# PAGE1.net
KiCad netlist of a schematic drawn in Altium Designer
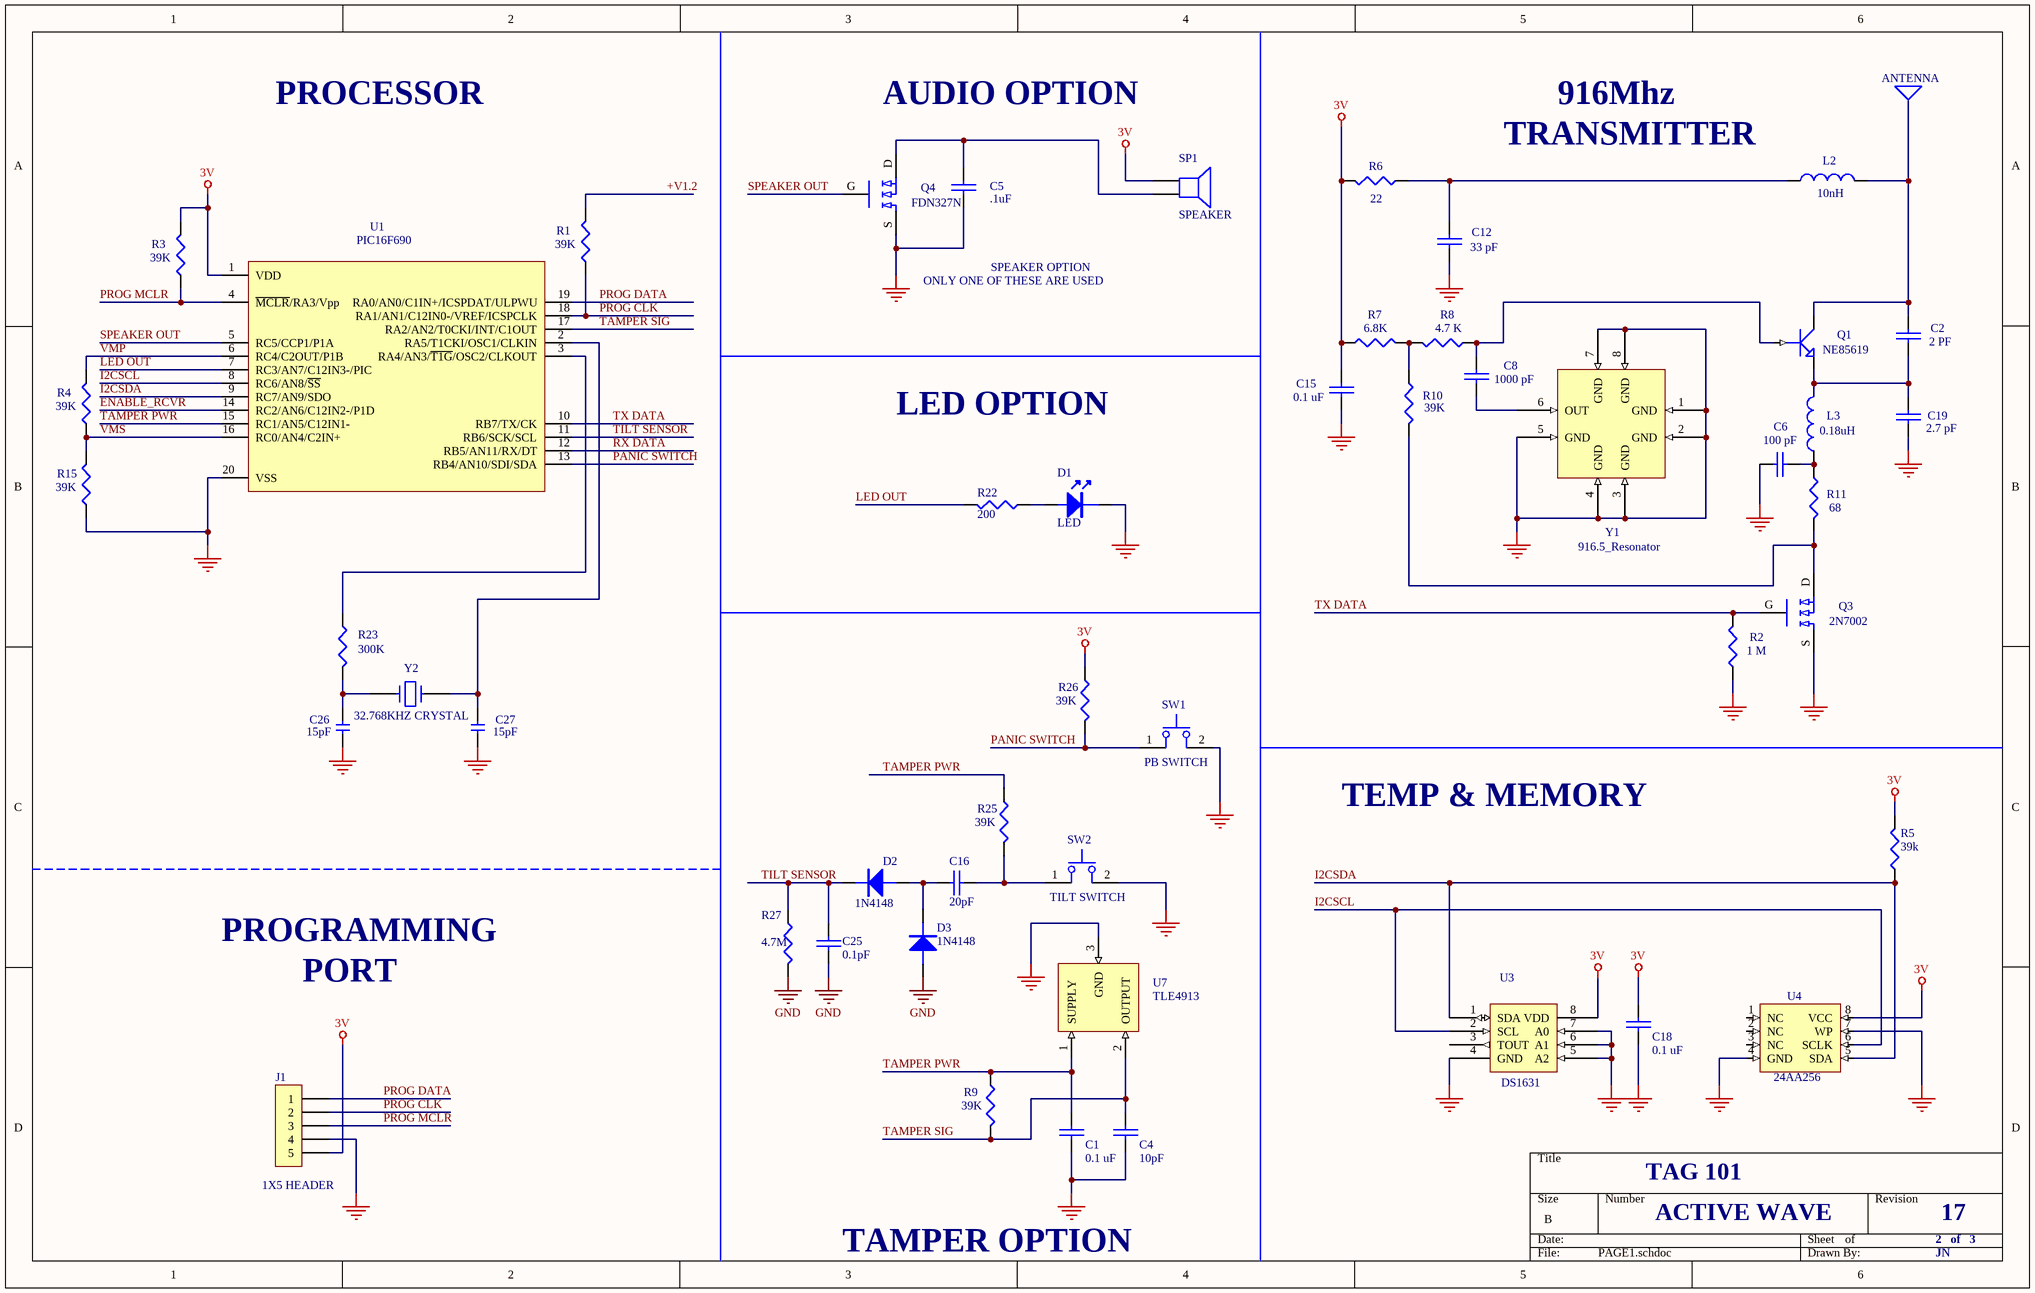
[diagram p0: PAGE1.schdoc]

(export (version "E")
  (design (tool "Eeschema 10.0.6"))
  (components
    (comp (ref "C1")
      (value "0.1 uF")
      (footprint "0603")
      (description "Capacitor")
      (libsource (lib "*") (part "CAP"))
    )
    (comp (ref "C2")
      (value "2 PF")
      (footprint "0603")
      (description "Capacitor")
      (libsource (lib "*") (part "CAP"))
    )
    (comp (ref "C4")
      (value "10pF")
      (footprint "0603")
      (description "Capacitor")
      (libsource (lib "*") (part "CAP"))
    )
    (comp (ref "C5")
      (value ".1uF")
      (footprint "0603")
      (description "Capacitor")
      (libsource (lib "*") (part "CAP"))
    )
    (comp (ref "C6")
      (value "100 pF")
      (footprint "0603")
      (description "Capacitor")
      (libsource (lib "*") (part "CAP"))
    )
    (comp (ref "C8")
      (value "1000 pF")
      (footprint "0603")
      (description "Capacitor")
      (libsource (lib "*") (part "CAP"))
    )
    (comp (ref "C12")
      (value "33 pF")
      (footprint "0603")
      (description "Capacitor")
      (libsource (lib "*") (part "CAP"))
    )
    (comp (ref "C15")
      (value "0.1 uF")
      (footprint "0603")
      (description "Capacitor")
      (libsource (lib "*") (part "CAP"))
    )
    (comp (ref "C16")
      (value "20pF")
      (footprint "0603")
      (description "Capacitor")
      (libsource (lib "*") (part "CAP"))
    )
    (comp (ref "C18")
      (value "0.1 uF")
      (footprint "0603")
      (description "Capacitor")
      (libsource (lib "*") (part "CAP"))
    )
    (comp (ref "C19")
      (value "2.7 pF")
      (footprint "0603")
      (description "Capacitor")
      (libsource (lib "*") (part "CAP"))
    )
    (comp (ref "C25")
      (value "0.1pF")
      (footprint "0603")
      (description "Capacitor")
      (libsource (lib "*") (part "CAP"))
    )
    (comp (ref "C26") (value "15pF") (footprint "0603") (libsource (lib "*") (part "C")))
    (comp (ref "C27") (value "15pF") (footprint "0603") (libsource (lib "*") (part "C")))
    (comp (ref "D1") (value "LED") (footprint "LED STANLEY H_1105W") (libsource (lib "*") (part "LED")))
    (comp (ref "D2")
      (value "1N4148")
      (footprint "sod123_021405")
      (description "Diode")
      (libsource (lib "*") (part "DIODE"))
    )
    (comp (ref "D3")
      (value "1N4148")
      (footprint "sod123_021405")
      (description "Diode")
      (libsource (lib "*") (part "DIODE"))
    )
    (comp (ref "J1")
      (value "1X5 HEADER")
      (footprint "1X5 HEADER")
      (description "Connector")
      (libsource (lib "*") (part "CON5"))
    )
    (comp (ref "L2") (value "10nH") (footprint "0603") (libsource (lib "*") (part "INDUCTOR")))
    (comp (ref "L3") (value "0.18uH") (footprint "0603") (libsource (lib "*") (part "INDUCTOR")))
    (comp (ref "Q1")
      (value "NE85619")
      (footprint "3 PIN ULTRA SUPER MINI MOLD")
      (description "NPN Transistor")
      (libsource (lib "*") (part "NPN1"))
    )
    (comp (ref "Q3") (value "2N7002") (libsource (lib "*") (part "FET 2")))
    (comp (ref "Q4") (value "FDN327N") (libsource (lib "*") (part "FET 2")))
    (comp (ref "R1") (value "39K") (footprint "0603") (libsource (lib "*") (part "RESISTOR")))
    (comp (ref "R2") (value "1 M") (footprint "0603") (libsource (lib "*") (part "RESISTOR")))
    (comp (ref "R3") (value "39K") (footprint "0603") (libsource (lib "*") (part "RESISTOR")))
    (comp (ref "R4") (value "39K") (footprint "0603") (libsource (lib "*") (part "RESISTOR")))
    (comp (ref "R5") (value "39k") (footprint "0603") (libsource (lib "*") (part "RESISTOR")))
    (comp (ref "R6") (value "22") (footprint "0603") (libsource (lib "*") (part "RESISTOR")))
    (comp (ref "R7") (value "6.8K") (footprint "0603") (libsource (lib "*") (part "RESISTOR")))
    (comp (ref "R8") (value "4.7 K") (footprint "0603") (libsource (lib "*") (part "RESISTOR")))
    (comp (ref "R9") (value "39K") (footprint "0603") (libsource (lib "*") (part "RESISTOR")))
    (comp (ref "R10") (value "39K") (footprint "0603") (libsource (lib "*") (part "RESISTOR")))
    (comp (ref "R11") (value "68") (footprint "0603") (libsource (lib "*") (part "RES1")))
    (comp (ref "R15") (value "39K") (footprint "0603") (libsource (lib "*") (part "RESISTOR")))
    (comp (ref "R22") (value "200") (footprint "0603") (libsource (lib "*") (part "RES1")))
    (comp (ref "R23") (value "300K") (footprint "0603") (libsource (lib "*") (part "RESISTOR")))
    (comp (ref "R25") (value "39K") (footprint "0603") (libsource (lib "*") (part "RESISTOR")))
    (comp (ref "R26") (value "39K") (footprint "0603") (libsource (lib "*") (part "RESISTOR")))
    (comp (ref "R27") (value "4.7M") (footprint "0603") (libsource (lib "*") (part "RESISTOR")))
    (comp (ref "SP1") (value "SPEAKER") (footprint "SMT_1028-S-R") (libsource (lib "*") (part "SPEAKER")))
    (comp (ref "SW1")
      (value "PB SWITCH")
      (footprint "SWITCH PB REVERSED_082907")
      (libsource (lib "Common") (part "SWITCH PB"))
    )
    (comp (ref "SW2")
      (value "TILT SWITCH")
      (footprint "SQ-SEN-200")
      (libsource (lib "Common") (part "SWITCH PB"))
    )
    (comp (ref "U1") (value "PIC16F690") (libsource (lib "*") (part "PIC16F690")))
    (comp (ref "U3") (value "DS1631") (footprint "SO8 SMALL") (libsource (lib "*") (part "DS1631")))
    (comp (ref "U4") (value "24AA256") (footprint "SO8") (libsource (lib "*") (part "24AA256")))
    (comp (ref "U7") (value "TLE4913") (footprint "SOT23W") (libsource (lib "*") (part "HALL EFFECT SWITCH")))
    (comp (ref "Y1")
      (value "916.5_Resonator")
      (footprint "RESONATOR")
      (libsource (lib "*") (part "RESONATOR"))
    )
    (comp (ref "Y2")
      (value "32.768KHZ CRYSTAL")
      (footprint "CRYSTAL ABRACON ABS07")
      (description "Crystal")
      (libsource (lib "*") (part "CRYSTAL"))
    )
  )
  (nets
    (net (code "1") (name "/+V1.2") (class "Default")
      (node (ref "R1") (pin "2") (pinfunction "2_2") (pintype "passive"))
    )
    (net (code "2") (name "/ENABLE_RCVR") (class "Default")
      (node (ref "U1") (pin "14") (pinfunction "RC2/AN6/C12IN2-/P1D_14") (pintype "passive"))
    )
    (net (code "3") (name "/I2CSCL") (class "Default")
      (node (ref "U1") (pin "8") (pinfunction "RC6/AN8/~{SS}_8") (pintype "passive"))
      (node (ref "U3") (pin "2") (pinfunction "SCL_2") (pintype "input"))
      (node (ref "U4") (pin "6") (pinfunction "SCLK_6") (pintype "input"))
    )
    (net (code "4") (name "/I2CSDA") (class "Default")
      (node (ref "R5") (pin "1") (pinfunction "1_1") (pintype "passive"))
      (node (ref "U1") (pin "9") (pinfunction "RC7/AN9/SDO_9") (pintype "passive"))
      (node (ref "U3") (pin "1") (pinfunction "SDA_1") (pintype "bidirectional"))
      (node (ref "U4") (pin "5") (pinfunction "SDA_5") (pintype "input"))
    )
    (net (code "5") (name "/LED OUT") (class "Default")
      (node (ref "R22") (pin "2") (pinfunction "2_2") (pintype "passive"))
      (node (ref "U1") (pin "7") (pinfunction "RC3/AN7/C12IN3-/PIC_7") (pintype "passive"))
    )
    (net (code "6") (name "/PANIC SWITCH") (class "Default")
      (node (ref "R26") (pin "2") (pinfunction "2_2") (pintype "passive"))
      (node (ref "SW1") (pin "1") (pinfunction "1_1") (pintype "passive"))
      (node (ref "U1") (pin "13") (pinfunction "RB4/AN10/SDI/SDA_13") (pintype "passive"))
    )
    (net (code "7") (name "/PROG CLK") (class "Default")
      (node (ref "J1") (pin "2") (pinfunction "2_2") (pintype "passive"))
      (node (ref "R1") (pin "1") (pinfunction "1_1") (pintype "passive"))
      (node (ref "U1") (pin "18") (pinfunction "RA1/AN1/C12IN0-/VREF/ICSPCLK_18") (pintype "passive"))
    )
    (net (code "8") (name "/PROG DATA") (class "Default")
      (node (ref "J1") (pin "1") (pinfunction "1_1") (pintype "passive"))
      (node (ref "U1") (pin "19") (pinfunction "RA0/AN0/C1IN+/ICSPDAT/ULPWU_19") (pintype "passive"))
    )
    (net (code "9") (name "/PROG MCLR") (class "Default")
      (node (ref "J1") (pin "3") (pinfunction "3_3") (pintype "passive"))
      (node (ref "R3") (pin "1") (pinfunction "1_1") (pintype "passive"))
      (node (ref "U1") (pin "4") (pinfunction "~{MCLR}/RA3/Vpp_4") (pintype "passive"))
    )
    (net (code "10") (name "/RX DATA") (class "Default")
      (node (ref "U1") (pin "12") (pinfunction "RB5/AN11/RX/DT_12") (pintype "passive"))
    )
    (net (code "11") (name "/SPEAKER OUT") (class "Default")
      (node (ref "Q4") (pin "G") (pinfunction "G_G") (pintype "passive"))
      (node (ref "U1") (pin "5") (pinfunction "RC5/CCP1/P1A_5") (pintype "passive"))
    )
    (net (code "12") (name "/TAMPER PWR") (class "Default")
      (node (ref "C1") (pin "1") (pinfunction "1_1") (pintype "passive"))
      (node (ref "R25") (pin "1") (pinfunction "1_1") (pintype "passive"))
      (node (ref "R9") (pin "1") (pinfunction "1_1") (pintype "passive"))
      (node (ref "U1") (pin "15") (pinfunction "RC1/AN5/C12IN1-_15") (pintype "passive"))
      (node (ref "U7") (pin "1") (pinfunction "SUPPLY_1") (pintype "input"))
    )
    (net (code "13") (name "/TAMPER SIG") (class "Default")
      (node (ref "C4") (pin "1") (pinfunction "1_1") (pintype "passive"))
      (node (ref "R9") (pin "2") (pinfunction "2_2") (pintype "passive"))
      (node (ref "U1") (pin "17") (pinfunction "RA2/AN2/T0CKI/INT/C1OUT_17") (pintype "passive"))
      (node (ref "U7") (pin "2") (pinfunction "OUTPUT_2") (pintype "input"))
    )
    (net (code "14") (name "/TILT SENSOR") (class "Default")
      (node (ref "C25") (pin "1") (pinfunction "1_1") (pintype "passive"))
      (node (ref "D2") (pin "K") (pinfunction "K_K") (pintype "passive"))
      (node (ref "R27") (pin "1") (pinfunction "1_1") (pintype "passive"))
      (node (ref "U1") (pin "11") (pinfunction "RB6/SCK/SCL_11") (pintype "passive"))
    )
    (net (code "15") (name "/TX DATA") (class "Default")
      (node (ref "Q3") (pin "G") (pinfunction "G_G") (pintype "passive"))
      (node (ref "R2") (pin "2") (pinfunction "2_2") (pintype "passive"))
      (node (ref "U1") (pin "10") (pinfunction "RB7/TX/CK_10") (pintype "passive"))
    )
    (net (code "16") (name "/VMP") (class "Default")
      (node (ref "R4") (pin "2") (pinfunction "2_2") (pintype "passive"))
      (node (ref "U1") (pin "6") (pinfunction "RC4/C2OUT/P1B_6") (pintype "passive"))
    )
    (net (code "17") (name "/VMS") (class "Default")
      (node (ref "R15") (pin "2") (pinfunction "2_2") (pintype "passive"))
      (node (ref "R4") (pin "1") (pinfunction "1_1") (pintype "passive"))
      (node (ref "U1") (pin "16") (pinfunction "RC0/AN4/C2IN+_16") (pintype "passive"))
    )
    (net (code "18") (name "3V") (class "Default")
      (node (ref "C15") (pin "1") (pinfunction "1_1") (pintype "passive"))
      (node (ref "C18") (pin "1") (pinfunction "1_1") (pintype "passive"))
      (node (ref "J1") (pin "5") (pinfunction "5_5") (pintype "passive"))
      (node (ref "R26") (pin "1") (pinfunction "1_1") (pintype "passive"))
      (node (ref "R3") (pin "2") (pinfunction "2_2") (pintype "passive"))
      (node (ref "R5") (pin "2") (pinfunction "2_2") (pintype "passive"))
      (node (ref "R6") (pin "2") (pinfunction "2_2") (pintype "passive"))
      (node (ref "R7") (pin "1") (pinfunction "1_1") (pintype "passive"))
      (node (ref "SP1") (pin "1") (pinfunction "1_1") (pintype "passive"))
      (node (ref "U1") (pin "1") (pinfunction "VDD_1") (pintype "passive"))
      (node (ref "U3") (pin "8") (pinfunction "VDD_8") (pintype "power_in"))
      (node (ref "U4") (pin "8") (pinfunction "VCC_8") (pintype "input"))
    )
    (net (code "19") (name "GND") (class "Default")
      (node (ref "C1") (pin "2") (pinfunction "2_2") (pintype "passive"))
      (node (ref "C12") (pin "2") (pinfunction "2_2") (pintype "passive"))
      (node (ref "C15") (pin "2") (pinfunction "2_2") (pintype "passive"))
      (node (ref "C18") (pin "2") (pinfunction "2_2") (pintype "passive"))
      (node (ref "C19") (pin "2") (pinfunction "2_2") (pintype "passive"))
      (node (ref "C25") (pin "2") (pinfunction "2_2") (pintype "passive"))
      (node (ref "C26") (pin "1") (pinfunction "1_1") (pintype "passive"))
      (node (ref "C27") (pin "1") (pinfunction "1_1") (pintype "passive"))
      (node (ref "C4") (pin "2") (pinfunction "2_2") (pintype "passive"))
      (node (ref "C5") (pin "2") (pinfunction "2_2") (pintype "passive"))
      (node (ref "C6") (pin "1") (pinfunction "1_1") (pintype "passive"))
      (node (ref "D1") (pin "K") (pinfunction "K_K") (pintype "passive"))
      (node (ref "D3") (pin "A") (pinfunction "A_A") (pintype "passive"))
      (node (ref "J1") (pin "4") (pinfunction "4_4") (pintype "passive"))
      (node (ref "Q3") (pin "S") (pinfunction "S_S") (pintype "passive"))
      (node (ref "Q4") (pin "S") (pinfunction "S_S") (pintype "passive"))
      (node (ref "R15") (pin "1") (pinfunction "1_1") (pintype "passive"))
      (node (ref "R2") (pin "1") (pinfunction "1_1") (pintype "passive"))
      (node (ref "R27") (pin "2") (pinfunction "2_2") (pintype "passive"))
      (node (ref "SW1") (pin "2") (pinfunction "2_2") (pintype "passive"))
      (node (ref "SW2") (pin "2") (pinfunction "2_2") (pintype "passive"))
      (node (ref "U1") (pin "20") (pinfunction "VSS_20") (pintype "passive"))
      (node (ref "U3") (pin "4") (pinfunction "GND_4") (pintype "power_in"))
      (node (ref "U3") (pin "5") (pinfunction "A2_5") (pintype "input"))
      (node (ref "U3") (pin "6") (pinfunction "A1_6") (pintype "input"))
      (node (ref "U3") (pin "7") (pinfunction "A0_7") (pintype "input"))
      (node (ref "U4") (pin "4") (pinfunction "GND_4") (pintype "input"))
      (node (ref "U4") (pin "7") (pinfunction "WP_7") (pintype "input"))
      (node (ref "U7") (pin "3") (pinfunction "GND_3") (pintype "input"))
      (node (ref "Y1") (pin "1") (pinfunction "GND_1") (pintype "input"))
      (node (ref "Y1") (pin "2") (pinfunction "GND_2") (pintype "input"))
      (node (ref "Y1") (pin "3") (pinfunction "GND_3") (pintype "input"))
      (node (ref "Y1") (pin "4") (pinfunction "GND_4") (pintype "input"))
      (node (ref "Y1") (pin "5") (pinfunction "GND_5") (pintype "input"))
      (node (ref "Y1") (pin "7") (pinfunction "GND_7") (pintype "input"))
      (node (ref "Y1") (pin "8") (pinfunction "GND_8") (pintype "input"))
    )
    (net (code "20") (name "Net-(C2-Pad1)") (class "Default")
      (node (ref "C2") (pin "1") (pinfunction "1_1") (pintype "passive"))
      (node (ref "L2") (pin "2") (pinfunction "2_2") (pintype "passive"))
      (node (ref "Q1") (pin "C") (pinfunction "C_C") (pintype "passive"))
    )
    (net (code "21") (name "Net-(C5-Pad1)") (class "Default")
      (node (ref "C5") (pin "1") (pinfunction "1_1") (pintype "passive"))
      (node (ref "Q4") (pin "D") (pinfunction "D_D") (pintype "passive"))
      (node (ref "SP1") (pin "2") (pinfunction "2_2") (pintype "passive"))
    )
    (net (code "22") (name "Net-(C6-Pad2)") (class "Default")
      (node (ref "C6") (pin "2") (pinfunction "2_2") (pintype "passive"))
      (node (ref "L3") (pin "1") (pinfunction "1_1") (pintype "passive"))
      (node (ref "R11") (pin "1") (pinfunction "1_1") (pintype "passive"))
    )
    (net (code "23") (name "Net-(C8-Pad1)") (class "Default")
      (node (ref "C8") (pin "1") (pinfunction "1_1") (pintype "passive"))
      (node (ref "Q1") (pin "B") (pinfunction "B_B") (pintype "input"))
      (node (ref "R8") (pin "1") (pinfunction "1_1") (pintype "passive"))
    )
    (net (code "24") (name "Net-(C12-Pad1)") (class "Default")
      (node (ref "C12") (pin "1") (pinfunction "1_1") (pintype "passive"))
      (node (ref "L2") (pin "1") (pinfunction "1_1") (pintype "passive"))
      (node (ref "R6") (pin "1") (pinfunction "1_1") (pintype "passive"))
    )
    (net (code "25") (name "Net-(C16-Pad1)") (class "Default")
      (node (ref "C16") (pin "1") (pinfunction "1_1") (pintype "passive"))
      (node (ref "R25") (pin "2") (pinfunction "2_2") (pintype "passive"))
      (node (ref "SW2") (pin "1") (pinfunction "1_1") (pintype "passive"))
    )
    (net (code "26") (name "Net-(C16-Pad2)") (class "Default")
      (node (ref "C16") (pin "2") (pinfunction "2_2") (pintype "passive"))
      (node (ref "D2") (pin "A") (pinfunction "A_A") (pintype "passive"))
      (node (ref "D3") (pin "K") (pinfunction "K_K") (pintype "passive"))
    )
    (net (code "27") (name "Net-(C19-Pad1)") (class "Default")
      (node (ref "C19") (pin "1") (pinfunction "1_1") (pintype "passive"))
      (node (ref "C2") (pin "2") (pinfunction "2_2") (pintype "passive"))
      (node (ref "L3") (pin "2") (pinfunction "2_2") (pintype "passive"))
      (node (ref "Q1") (pin "E") (pinfunction "E_E") (pintype "passive"))
    )
    (net (code "28") (name "Net-(C26-Pad2)") (class "Default")
      (node (ref "C26") (pin "2") (pinfunction "2_2") (pintype "passive"))
      (node (ref "R23") (pin "2") (pinfunction "2_2") (pintype "passive"))
      (node (ref "Y2") (pin "2") (pinfunction "2_2") (pintype "passive"))
    )
    (net (code "29") (name "Net-(D1-PadA)") (class "Default")
      (node (ref "D1") (pin "A") (pinfunction "A_A") (pintype "passive"))
      (node (ref "R22") (pin "1") (pinfunction "1_1") (pintype "passive"))
    )
    (net (code "30") (name "Net-(Q3-PadD)") (class "Default")
      (node (ref "Q3") (pin "D") (pinfunction "D_D") (pintype "passive"))
      (node (ref "R10") (pin "2") (pinfunction "2_2") (pintype "passive"))
      (node (ref "R11") (pin "2") (pinfunction "2_2") (pintype "passive"))
    )
    (net (code "31") (name "Net-(R10-Pad1)") (class "Default")
      (node (ref "R10") (pin "1") (pinfunction "1_1") (pintype "passive"))
      (node (ref "R7") (pin "2") (pinfunction "2_2") (pintype "passive"))
      (node (ref "R8") (pin "2") (pinfunction "2_2") (pintype "passive"))
    )
    (net (code "32") (name "Net-(U1-RA4{slash}AN3{slash}~{T1G}{slash}OSC2{slash}CLKOUT)") (class "Default")
      (node (ref "R23") (pin "1") (pinfunction "1_1") (pintype "passive"))
      (node (ref "U1") (pin "3") (pinfunction "RA4/AN3/~{T1G}/OSC2/CLKOUT_3") (pintype "passive"))
    )
    (net (code "33") (name "Net-(U1-RA5{slash}T1CKI{slash}OSC1{slash}CLKIN)") (class "Default")
      (node (ref "C27") (pin "2") (pinfunction "2_2") (pintype "passive"))
      (node (ref "U1") (pin "2") (pinfunction "RA5/T1CKI/OSC1/CLKIN_2") (pintype "passive"))
      (node (ref "Y2") (pin "1") (pinfunction "1_1") (pintype "passive"))
    )
    (net (code "34") (name "Net-(Y1-OUT)") (class "Default")
      (node (ref "C8") (pin "2") (pinfunction "2_2") (pintype "passive"))
      (node (ref "Y1") (pin "6") (pinfunction "OUT_6") (pintype "input"))
    )
    (net (code "35") (name "unconnected-(U3-TOUT-Pad3)") (class "Default")
      (node (ref "U3") (pin "3") (pinfunction "TOUT_3") (pintype "output"))
    )
    (net (code "36") (name "unconnected-(U4-NC-Pad1)") (class "Default")
      (node (ref "U4") (pin "1") (pinfunction "NC_1") (pintype "input"))
    )
    (net (code "37") (name "unconnected-(U4-NC-Pad2)") (class "Default")
      (node (ref "U4") (pin "2") (pinfunction "NC_2") (pintype "input"))
    )
    (net (code "38") (name "unconnected-(U4-NC-Pad3)") (class "Default")
      (node (ref "U4") (pin "3") (pinfunction "NC_3") (pintype "input"))
    )
  )
)
